# power.net
KiCad netlist of a schematic drawn in Altium Designer
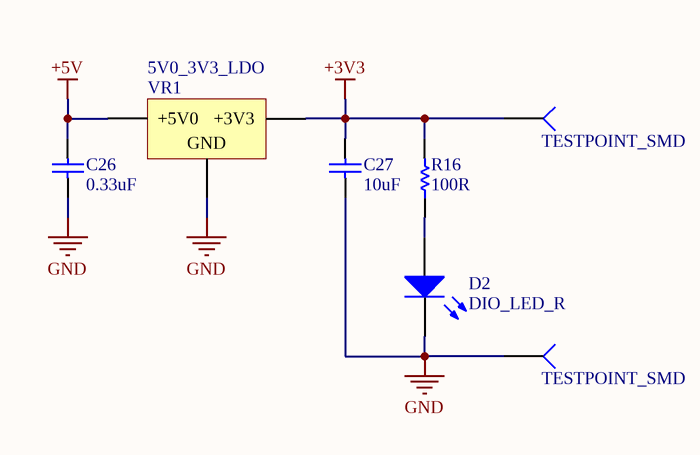
[diagram p0: power.SchDoc]

(export (version "E")
  (design (tool "Eeschema 10.0.6"))
  (components
    (comp (ref "3V3")
      (value "TESTPOINT_SMD")
      (footprint "TESTPOINT")
      (libsource (lib "UWRT_Schematic_Library_2019") (part "TESTPOINT_SMD"))
    )
    (comp (ref "C26")
      (value "0.33uF")
      (footprint "CAPC0603(1608)55_N")
      (description "CAP CER 0.33UF 16V X7R 0603")
      (fields
        (field (name "PART NUMBER") "GRM188R71C334KA01D")
        (field (name "MANUFACTURER") "Murata Electronics North America")
      )
      (libsource (lib "UWRT_Schematic_Library_2019") (part "CAP_0.33uF_16V_0603"))
    )
    (comp (ref "C27")
      (value "10uF")
      (footprint "CAPC0603(1608)55_N")
      (description "CAP CER 10UF 10V X5R 0603")
      (fields (field (name "PART NUMBER") "CC0603MRX5R6BB106") (field (name "MANUFACTURER") "Yageo"))
      (libsource (lib "UWRT_Schematic_Library_2019") (part "CAP_10uF_0603"))
    )
    (comp (ref "D2")
      (value "DIO_LED_R")
      (footprint "LED_0805")
      (description "LED RED DIFFUSED 0805 SMD")
      (fields (field (name "PART NUMBER") "LS R976-NR-1") (field (name "MANUFACTURER") "OSRAM"))
      (libsource (lib "UWRT_Schematic_Library_2019") (part "DIO_LED_R"))
    )
    (comp (ref "GND")
      (value "TESTPOINT_SMD")
      (footprint "TESTPOINT")
      (libsource (lib "UWRT_Schematic_Library_2019") (part "TESTPOINT_SMD"))
    )
    (comp (ref "R16")
      (value "100R")
      (footprint "RESC0603(1608)_N")
      (description "RES SMD 100 OHM 1% 1/10W 0603")
      (fields (field (name "MANUFACTURER") "Yageo") (field (name "TOLERANCE") "1%"))
      (libsource (lib "UWRT_Schematic_Library_2019") (part "RES_100R_0603"))
    )
    (comp (ref "VR1")
      (value "5V0_3V3_LDO")
      (footprint "UWRT_Footprint_Library_2019:VOLTAGE_REGULATOR")
      (description "IC REG LINEAR 3.3V 1A DPAK")
      (fields (field (name "PART NUMBER") "NCP1117DT33T5G") (field (name "MANUFACTURER") "ON Semiconductor"))
      (libsource (lib "UWRT_Schematic_Library_2019") (part "5V0_3V3_LDO"))
    )
  )
  (nets
    (net (code "1") (name "+3V3") (class "Default")
      (node (ref "3V3") (pin "1") (pinfunction "=value_1") (pintype "passive"))
      (node (ref "C27") (pin "2") (pinfunction "2_2") (pintype "passive"))
      (node (ref "R16") (pin "2") (pinfunction "2_2") (pintype "passive"))
      (node (ref "VR1") (pin "2") (pinfunction "+3V3_2") (pintype "passive"))
    )
    (net (code "2") (name "+5V") (class "Default")
      (node (ref "C26") (pin "2") (pinfunction "2_2") (pintype "passive"))
      (node (ref "VR1") (pin "3") (pinfunction "+5V0_3") (pintype "passive"))
    )
    (net (code "3") (name "GND") (class "Default")
      (node (ref "C26") (pin "1") (pinfunction "1_1") (pintype "passive"))
      (node (ref "C27") (pin "1") (pinfunction "1_1") (pintype "passive"))
      (node (ref "D2") (pin "2") (pinfunction "K_2") (pintype "passive"))
      (node (ref "GND") (pin "1") (pinfunction "=value_1") (pintype "passive"))
      (node (ref "VR1") (pin "1") (pinfunction "GND_1") (pintype "passive"))
    )
    (net (code "4") (name "Net-(D2-A)") (class "Default")
      (node (ref "D2") (pin "1") (pinfunction "A_1") (pintype "passive"))
      (node (ref "R16") (pin "1") (pinfunction "1_1") (pintype "passive"))
    )
  )
)
